# FPGA_RESET.net
KiCad netlist of a schematic drawn in Altium Designer
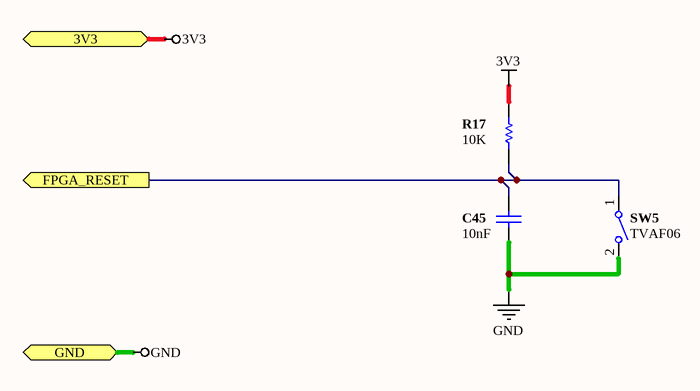
[diagram p0: FPGA_RESET.SchDoc]

(export (version "E")
  (design (tool "Eeschema 10.0.6"))
  (components
    (comp (ref "C45")
      (value "10nF")
      (footprint "CAPC0402(1005)60_N")
      (description "CAP 10nF 6.3V ?0% 0402 (1005 Metric) Thickness 0.6mm SMD")
      (fields (field (name "TOLERANCE") "?0%") (field (name "Comment") "CAP 10nF 6.3V 0402(1005)"))
      (libsource (lib "Altium Content Vault") (part "CMP-1034-01869-1"))
    )
    (comp (ref "R17")
      (value "10K")
      (footprint "RESC0402(1005)_N")
      (description "10K 0.063W 1% 0402 (1005 Metric)  SMD")
      (fields (field (name "TOLERANCE") "1 %") (field (name "POWER") "0.063 W"))
      (libsource (lib "Altium Content Vault") (part "CMP-1011-00623-1"))
    )
    (comp (ref "SW5")
      (value "TVAF06")
      (footprint "JNFU-TVAF06-2")
      (description "Switch, SPST Push Button, 50mA, 12V DC, SMD")
      (libsource (lib "Altium Content Vault") (part "SW_SPST-2"))
    )
  )
  (nets
    (net (code "1") (name "/FPGA_RESET") (class "Default")
      (node (ref "C45") (pin "1") (pinfunction "1_1") (pintype "passive"))
      (node (ref "R17") (pin "2") (pinfunction "2_2") (pintype "passive"))
      (node (ref "SW5") (pin "1") (pinfunction "A1_1") (pintype "passive"))
    )
    (net (code "2") (name "3V3") (class "Default")
      (node (ref "R17") (pin "1") (pinfunction "1_1") (pintype "passive"))
    )
    (net (code "3") (name "GND") (class "Default")
      (node (ref "C45") (pin "2") (pinfunction "2_2") (pintype "passive"))
      (node (ref "SW5") (pin "2") (pinfunction "B1_2") (pintype "passive"))
    )
  )
)
